# 03_Heater_Control.net
KiCad netlist of a schematic drawn in Altium Designer
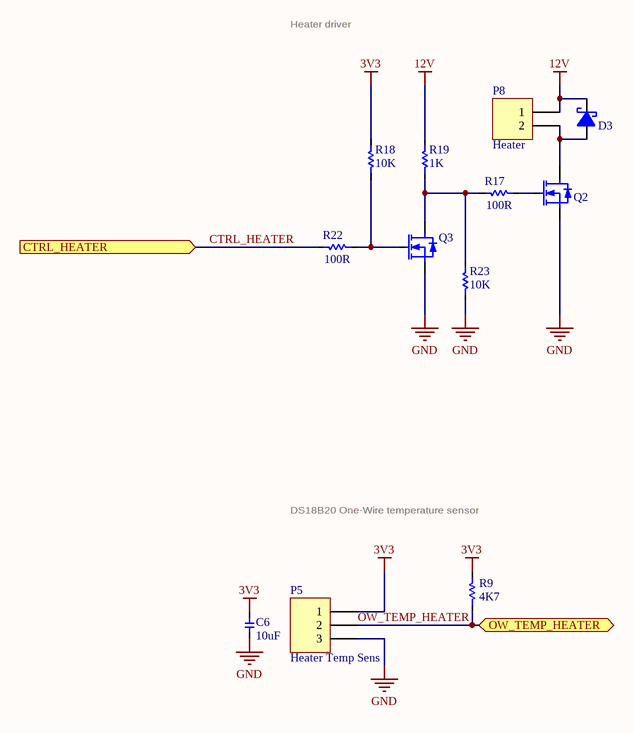
[diagram p0: 03_Heater_Control.SchDoc]

(export (version "E")
  (design (tool "Eeschema 10.0.6"))
  (components
    (comp (ref "C6")
      (value "10uF")
      (footprint "Moji Footprintovi:0603 - CAP HS")
      (description "Capacitor")
      (fields
        (field (name "MANUFACTURER") "Samsung Electro-Mechanics")
        (field (name "MANUFACTURER PART NUMBER") "CL10A106MO8NQNC")
      )
      (libsource (lib "Moji Schematici (1)") (part "Cap"))
    )
    (comp (ref "D3")
      (value "Diode Schotky")
      (footprint "Moji Footprintovi:SOD123F")
      (fields
        (field (name "MANUFACTURER") "Nexperia USA Inc.")
        (field (name "MANUFACTURER PART NUMBER") "PMEG6010CEH,115")
        (field (name "DISTRIBUTOR PART NUMBER") "1727-3848-1-ND")
      )
      (libsource (lib "Moji Schematici (1)") (part "Diode Schotky"))
    )
    (comp (ref "P5")
      (value "Heater Temp Sens")
      (footprint "Moji Footprintovi:Header 3x1")
      (description "Header, 3-Pin")
      (libsource (lib "Schematic_Misc") (part "Header 3"))
    )
    (comp (ref "P8")
      (value "Heater")
      (footprint "Moji Footprintovi:Header 2x1")
      (description "Header, 2-Pin")
      (libsource (lib "Schematic_Misc") (part "Header 2"))
    )
    (comp (ref "Q2")
      (value "PSMN9R1-30YL")
      (footprint "Moji Footprintovi:LFPAK-8")
      (description "MOSFET N-CH 30V 37A LFPAK")
      (fields
        (field (name "MANUFACTURER") "Nexperia USA Inc.")
        (field (name "MANUFACTURER PART NUMBER") "PSMN011-30YLC,115")
      )
      (libsource (lib "Schematic_Misc") (part "PSMN9R1-30YL"))
    )
    (comp (ref "Q3")
      (value "DMN62D0U-13")
      (footprint "Moji Footprintovi:SOT90P240X100-3N")
      (description "MOSFET N-CH 60V 0.38A")
      (fields
        (field (name "MANUFACTURER") "Diodes Incorporated")
        (field (name "DISTRIBUTOR PART NUMBER") "DMN62D0U-13DICT-ND")
      )
      (libsource (lib "Moji Schematici (1)") (part "DMN62D0U-13"))
    )
    (comp (ref "R9")
      (value "4K7")
      (footprint "Footprint_Misc:0603 - HS")
      (description "Resistor")
      (fields
        (field (name "DISTRIBUTOR PART NUMBER") "RMCF0603FT4K70CT-ND")
        (field (name "MANUFACTURER") "Stackpole Electronics Inc")
      )
      (libsource (lib "Moji Schematici (1)") (part "Res"))
    )
    (comp (ref "R17")
      (value "100R")
      (footprint "Footprint_Misc:0603 - HS")
      (description "Resistor")
      (fields
        (field (name "DISTRIBUTOR PART NUMBER") "RMCF0603FT100RCT-ND")
        (field (name "MANUFACTURER") "Stackpole Electronics Inc")
      )
      (libsource (lib "Moji Schematici (1)") (part "Res"))
    )
    (comp (ref "R18")
      (value "10K")
      (footprint "Footprint_Misc:0603 - HS")
      (description "Resistor")
      (fields
        (field (name "DISTRIBUTOR PART NUMBER") "RMCF0603JT10K0CT-ND")
        (field (name "MANUFACTURER") "Stackpole Electronics Inc")
      )
      (libsource (lib "Moji Schematici (1)") (part "Res"))
    )
    (comp (ref "R19")
      (value "1K")
      (footprint "Footprint_Misc:0603 - HS")
      (description "Resistor")
      (fields
        (field (name "DISTRIBUTOR PART NUMBER") "RNCS0603BKE1K00CT-ND")
        (field (name "MANUFACTURER") "Stackpole Electronics Inc")
      )
      (libsource (lib "Moji Schematici (1)") (part "Res"))
    )
    (comp (ref "R22")
      (value "100R")
      (footprint "Footprint_Misc:0603 - HS")
      (description "Resistor")
      (fields
        (field (name "DISTRIBUTOR PART NUMBER") "RMCF0603FT100RCT-ND")
        (field (name "MANUFACTURER") "Stackpole Electronics Inc")
      )
      (libsource (lib "Moji Schematici (1)") (part "Res"))
    )
    (comp (ref "R23")
      (value "10K")
      (footprint "Footprint_Misc:0603 - HS")
      (description "Resistor")
      (fields
        (field (name "DISTRIBUTOR PART NUMBER") "RMCF0603JT10K0CT-ND")
        (field (name "MANUFACTURER") "Stackpole Electronics Inc")
      )
      (libsource (lib "Moji Schematici (1)") (part "Res"))
    )
  )
  (nets
    (net (code "1") (name "/CTRL_HEATER") (class "Default")
      (node (ref "R22") (pin "1") (pinfunction "1_1") (pintype "passive"))
    )
    (net (code "2") (name "/OW_TEMP_HEATER") (class "Default")
      (node (ref "P5") (pin "2") (pinfunction "2_2") (pintype "passive"))
      (node (ref "R9") (pin "2") (pinfunction "2_2") (pintype "passive"))
    )
    (net (code "3") (name "3V3") (class "Default")
      (node (ref "C6") (pin "1") (pinfunction "1_1") (pintype "passive"))
      (node (ref "P5") (pin "1") (pinfunction "1_1") (pintype "passive"))
      (node (ref "R18") (pin "1") (pinfunction "1_1") (pintype "passive"))
      (node (ref "R9") (pin "1") (pinfunction "1_1") (pintype "passive"))
    )
    (net (code "4") (name "12V") (class "Default")
      (node (ref "D3") (pin "K") (pinfunction "K_K") (pintype "passive"))
      (node (ref "P8") (pin "1") (pinfunction "1_1") (pintype "passive"))
      (node (ref "R19") (pin "1") (pinfunction "1_1") (pintype "passive"))
    )
    (net (code "5") (name "GND") (class "Default")
      (node (ref "C6") (pin "2") (pinfunction "2_2") (pintype "passive"))
      (node (ref "P5") (pin "3") (pinfunction "3_3") (pintype "passive"))
      (node (ref "Q2") (pin "S") (pinfunction "S_S") (pintype "passive"))
      (node (ref "Q3") (pin "2") (pinfunction "S_2") (pintype "passive"))
      (node (ref "R23") (pin "2") (pinfunction "2_2") (pintype "passive"))
    )
    (net (code "6") (name "Net-(D3-PadA)") (class "Default")
      (node (ref "D3") (pin "A") (pinfunction "A_A") (pintype "passive"))
      (node (ref "P8") (pin "2") (pinfunction "2_2") (pintype "passive"))
      (node (ref "Q2") (pin "D") (pinfunction "D_D") (pintype "passive"))
    )
    (net (code "7") (name "Net-(Q2-PadG)") (class "Default")
      (node (ref "Q2") (pin "G") (pinfunction "G_G") (pintype "passive"))
      (node (ref "R17") (pin "2") (pinfunction "2_2") (pintype "passive"))
    )
    (net (code "8") (name "Net-(Q3-D)") (class "Default")
      (node (ref "Q3") (pin "3") (pinfunction "D_3") (pintype "passive"))
      (node (ref "R17") (pin "1") (pinfunction "1_1") (pintype "passive"))
      (node (ref "R19") (pin "2") (pinfunction "2_2") (pintype "passive"))
      (node (ref "R23") (pin "1") (pinfunction "1_1") (pintype "passive"))
    )
    (net (code "9") (name "Net-(Q3-G)") (class "Default")
      (node (ref "Q3") (pin "1") (pinfunction "G_1") (pintype "passive"))
      (node (ref "R18") (pin "2") (pinfunction "2_2") (pintype "passive"))
      (node (ref "R22") (pin "2") (pinfunction "2_2") (pintype "passive"))
    )
  )
)
